# small_hopper_board.net
KiCad netlist of a schematic drawn in EAGLE
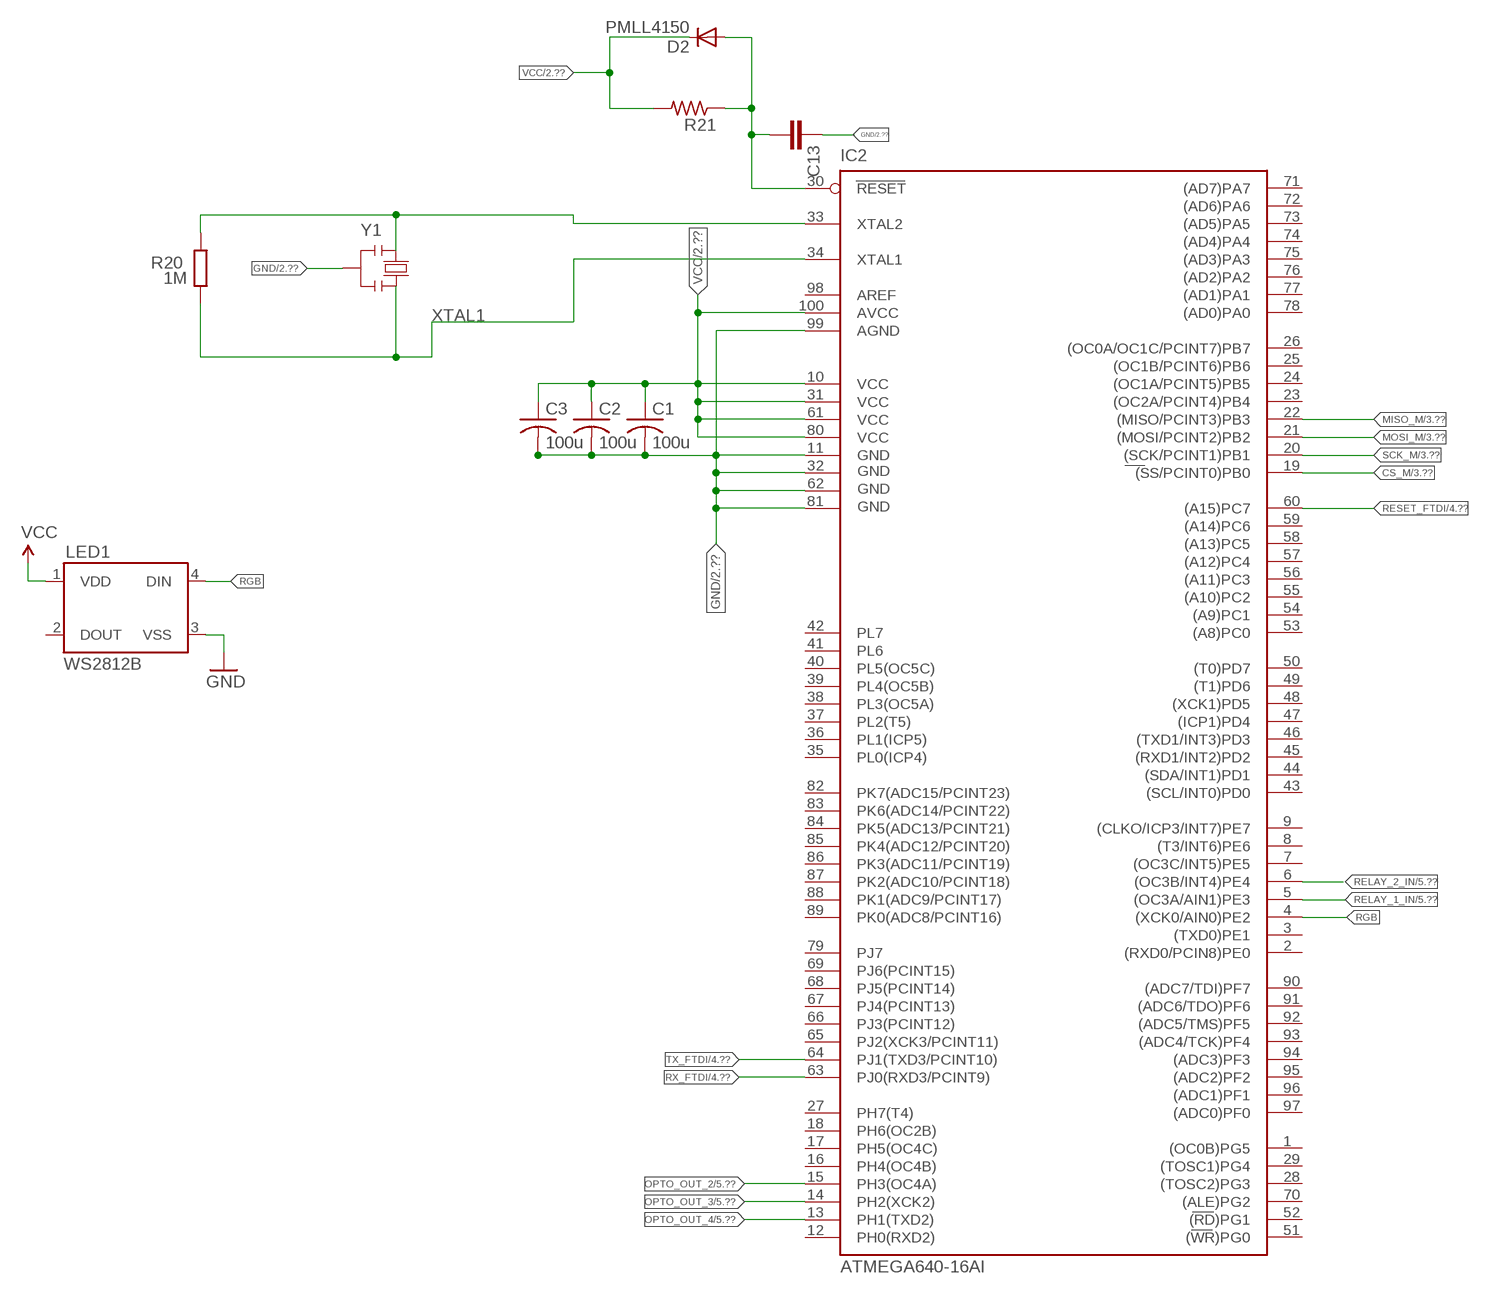
[diagram p0: schematic, sheet 1]
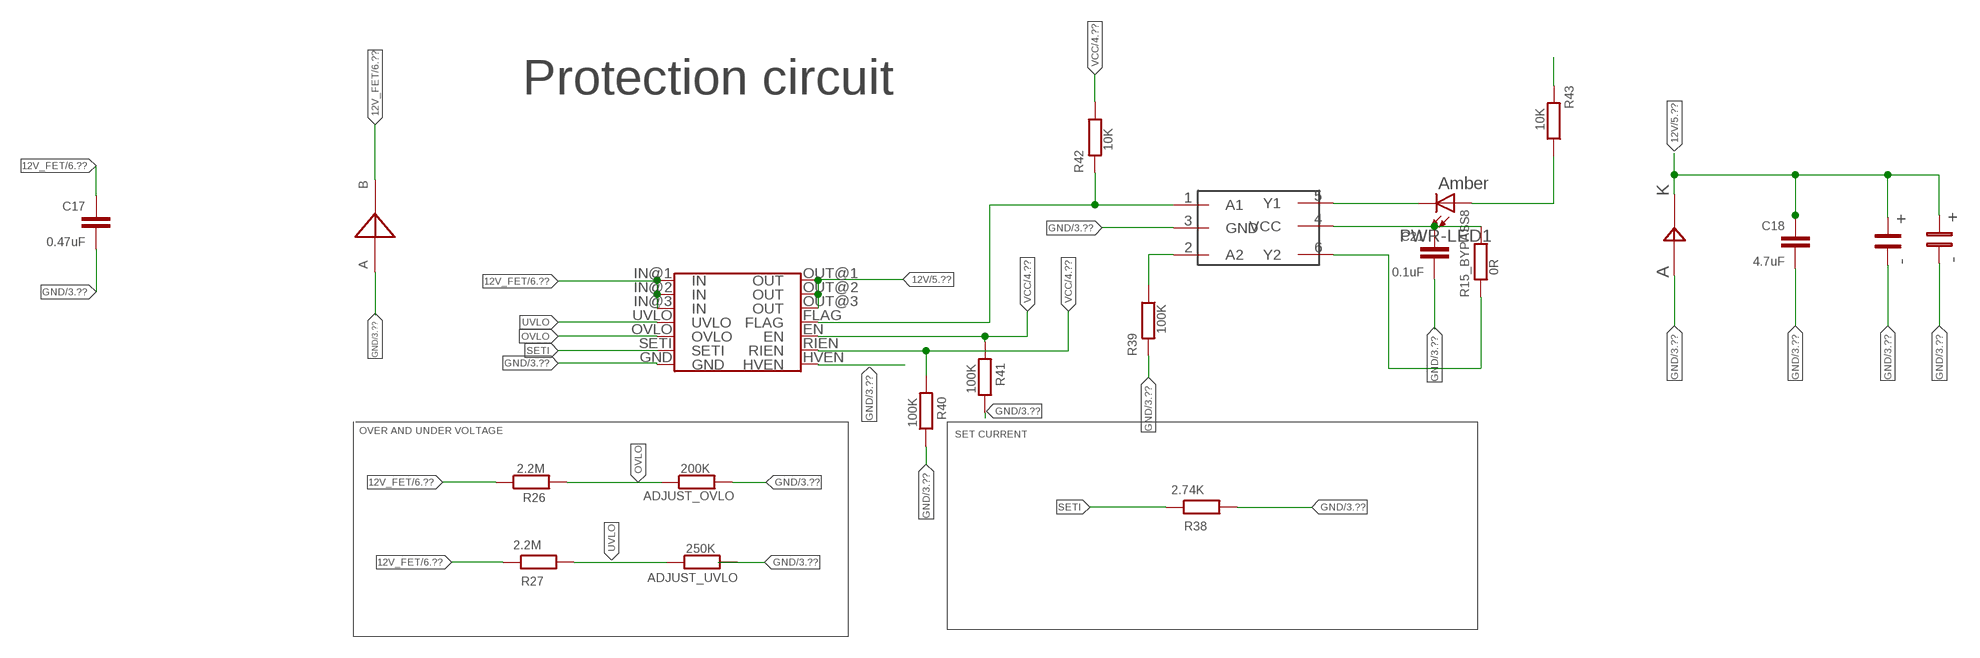
[diagram p1: schematic, sheet 2]
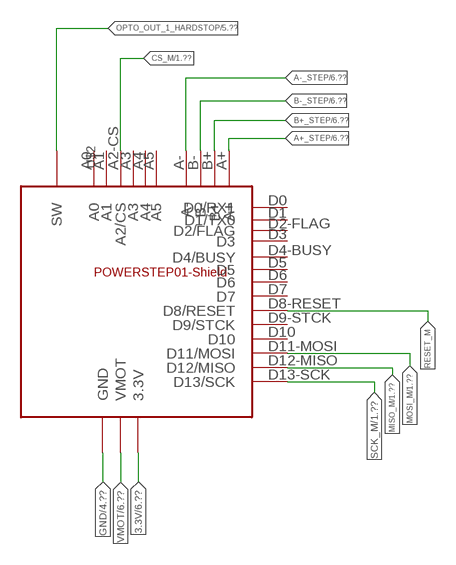
[diagram p2: schematic, sheet 3]
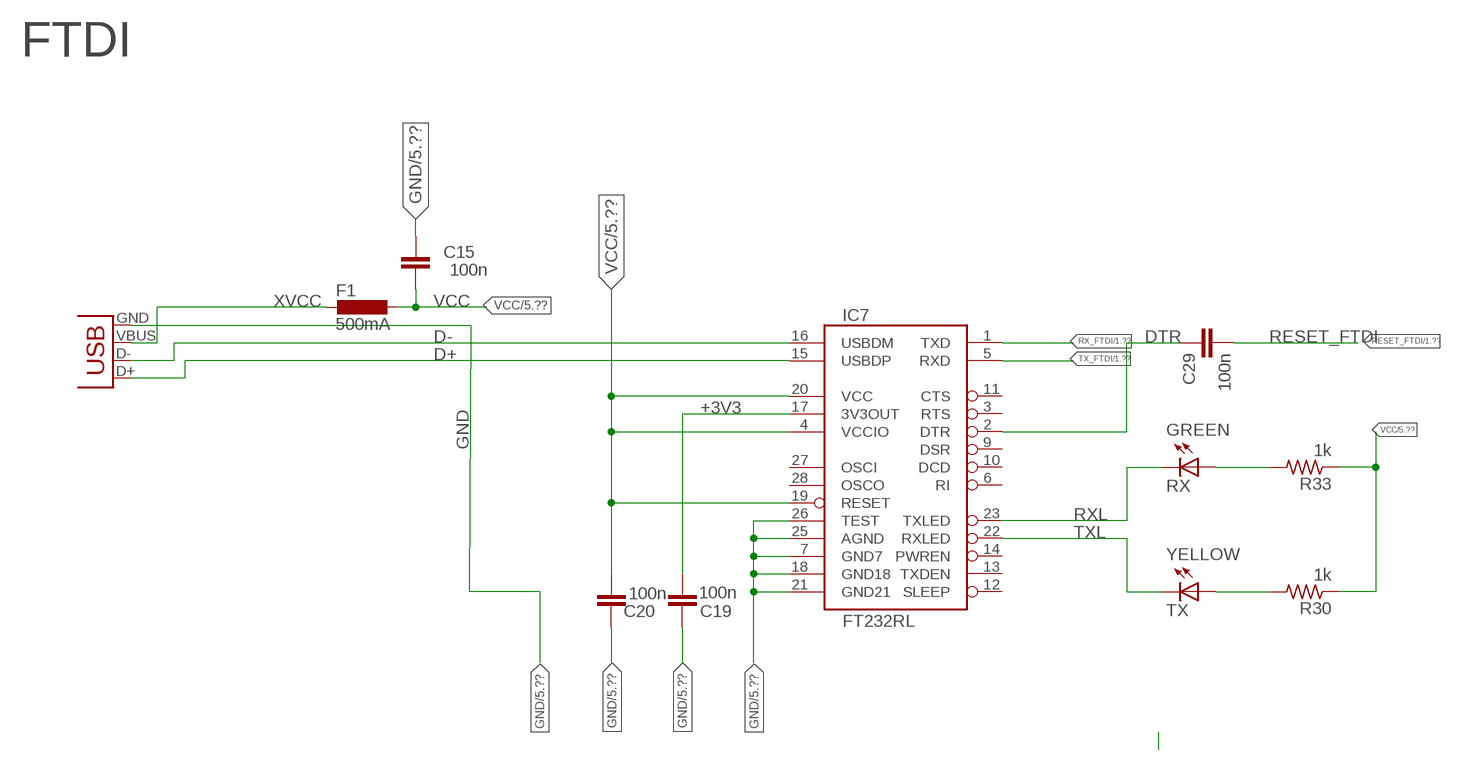
[diagram p3: schematic, sheet 4]
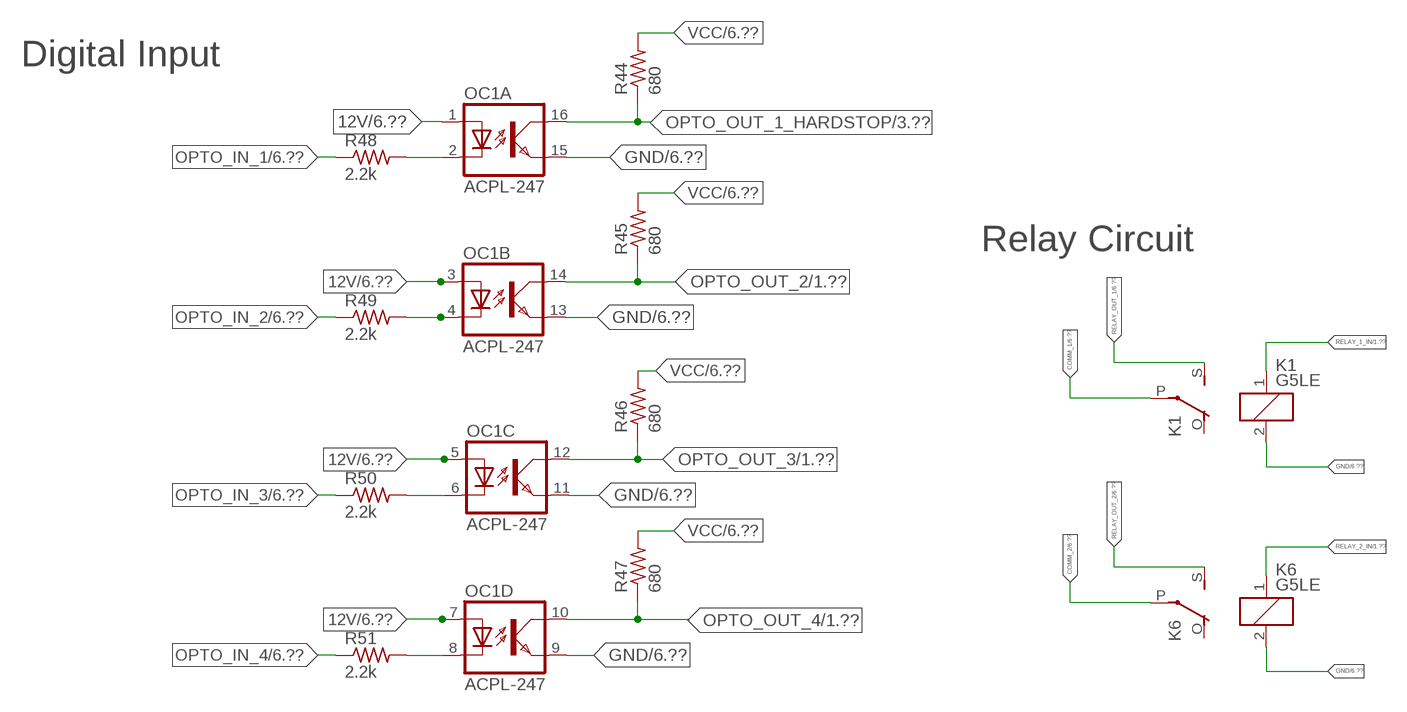
[diagram p4: schematic, sheet 5]
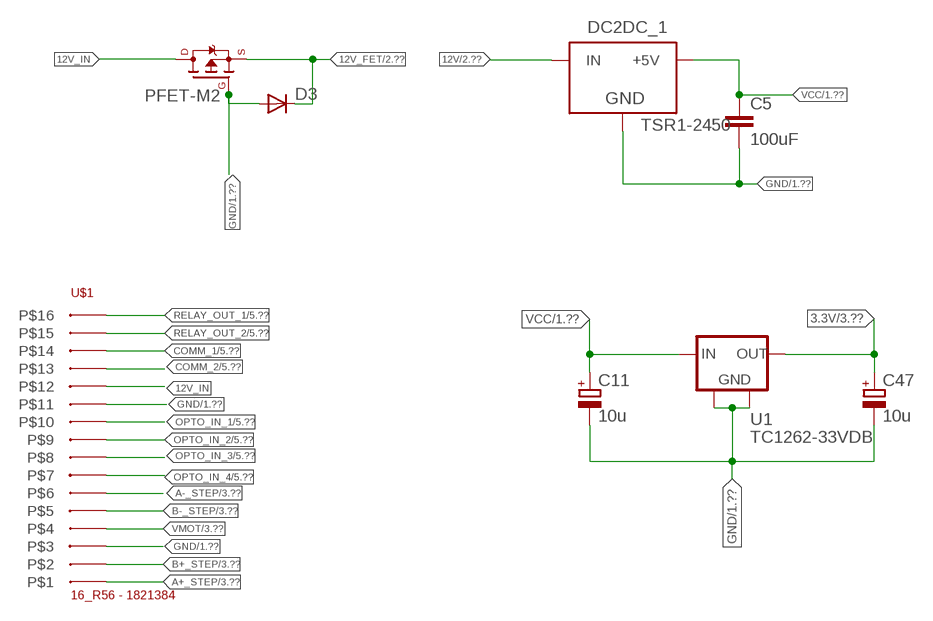
[diagram p5: schematic, sheet 6]

(export (version "E")
  (design (tool "Eeschema 10.0.6"))
  (components
    (comp (ref "C1")
      (value "100u")
      (footprint "eagle-import:C0603")
      (libsource (lib "eagle-import") (part "C-USC0603"))
    )
    (comp (ref "C2")
      (value "100u")
      (footprint "eagle-import:C0603")
      (libsource (lib "eagle-import") (part "C-USC0603"))
    )
    (comp (ref "C3")
      (value "100u")
      (footprint "eagle-import:C0603")
      (libsource (lib "eagle-import") (part "C-USC0603"))
    )
    (comp (ref "C13")
      (value "CC0603")
      (footprint "eagle-import:C0603")
      (libsource (lib "eagle-import") (part "CC0603"))
    )
    (comp (ref "D2")
      (value "PMLL4150")
      (footprint "eagle-import:SOD80C")
      (libsource (lib "eagle-import") (part "PMLL4150"))
    )
    (comp (ref "IC2")
      (value "ATMEGA640-16AI")
      (footprint "eagle-import:TQFP100")
      (libsource (lib "eagle-import") (part "ATMEGAAI640-16"))
    )
    (comp (ref "LED1")
      (value "WS2812B")
      (footprint "eagle-import:WS2812B")
      (libsource (lib "eagle-import") (part "WS2812B"))
    )
    (comp (ref "R20")
      (value "1M")
      (footprint "eagle-import:R0603-ROUND")
      (libsource (lib "eagle-import") (part "R-EU_R0603"))
    )
    (comp (ref "R21")
      (value "R-US_R0603")
      (footprint "eagle-import:R0603")
      (libsource (lib "eagle-import") (part "resistor_R-US_R0603"))
    )
    (comp (ref "Y1")
      (value "RESONATORMU")
      (footprint "eagle-import:RESONATOR")
      (libsource (lib "eagle-import") (part "RESONATORMU"))
    )
    (comp (ref "C5")
      (value "100uF")
      (footprint "eagle-import:C0603")
      (libsource (lib "eagle-import") (part "CC0603"))
    )
    (comp (ref "C11")
      (value "10u")
      (footprint "eagle-import:153CLV-0605")
      (libsource (lib "eagle-import") (part "CPOL-EU153CLV-0605"))
    )
    (comp (ref "C47")
      (value "10u")
      (footprint "eagle-import:153CLV-0605")
      (libsource (lib "eagle-import") (part "CPOL-EU153CLV-0605"))
    )
    (comp (ref "D3")
      (value "DIODE-MINIMELF")
      (footprint "eagle-import:MINIMELF")
      (libsource (lib "eagle-import") (part "DIODE-MINIMELF"))
    )
    (comp (ref "DC2DC_1")
      (value "TSR1-2450")
      (footprint "eagle-import:TSR-1")
      (libsource (lib "eagle-import") (part "TSR1-2450"))
    )
    (comp (ref "PFET-M2")
      (value "FQP47P06NORMAL")
      (footprint "eagle-import:FQP47P06-NORMAL")
      (libsource (lib "eagle-import") (part "FQP47P06NORMAL"))
    )
    (comp (ref "U$1")
      (value "16_R56 - 1821384")
      (footprint "eagle-import:16_R56 - 1821384")
      (libsource (lib "eagle-import") (part "16_R56 - 1821384"))
    )
    (comp (ref "U1")
      (value "TC1262-33VDB")
      (footprint "eagle-import:SOT223")
      (libsource (lib "eagle-import") (part "TC1262-50VDB"))
    )
    (comp (ref "K1")
      (value "G5LE")
      (footprint "eagle-import:G5LE")
      (libsource (lib "eagle-import") (part "G5LE"))
    )
    (comp (ref "K6")
      (value "G5LE")
      (footprint "eagle-import:G5LE")
      (libsource (lib "eagle-import") (part "G5LE"))
    )
    (comp (ref "OC1")
      (value "ACPL-247")
      (footprint "eagle-import:SOP16")
      (libsource (lib "eagle-import") (part "ACPL-247"))
    )
    (comp (ref "R44")
      (value "680")
      (footprint "eagle-import:R0603")
      (libsource (lib "eagle-import") (part "R-US_R0603"))
    )
    (comp (ref "R45")
      (value "680")
      (footprint "eagle-import:R0603")
      (libsource (lib "eagle-import") (part "R-US_R0603"))
    )
    (comp (ref "R46")
      (value "680")
      (footprint "eagle-import:R0603")
      (libsource (lib "eagle-import") (part "R-US_R0603"))
    )
    (comp (ref "R47")
      (value "680")
      (footprint "eagle-import:R0603")
      (libsource (lib "eagle-import") (part "R-US_R0603"))
    )
    (comp (ref "R48")
      (value "2.2k")
      (footprint "eagle-import:R0603")
      (libsource (lib "eagle-import") (part "R-US_R0603"))
    )
    (comp (ref "R49")
      (value "2.2k")
      (footprint "eagle-import:R0603")
      (libsource (lib "eagle-import") (part "R-US_R0603"))
    )
    (comp (ref "R50")
      (value "2.2k")
      (footprint "eagle-import:R0603")
      (libsource (lib "eagle-import") (part "R-US_R0603"))
    )
    (comp (ref "R51")
      (value "2.2k")
      (footprint "eagle-import:R0603")
      (libsource (lib "eagle-import") (part "R-US_R0603"))
    )
    (comp (ref "C15")
      (value "100n")
      (footprint "eagle-import:C0603")
      (libsource (lib "eagle-import") (part "rcl_C-EUC0603"))
    )
    (comp (ref "C19")
      (value "100n")
      (footprint "eagle-import:C0603-ROUND")
      (libsource (lib "eagle-import") (part "C-EU0603-RND"))
    )
    (comp (ref "C20")
      (value "100n")
      (footprint "eagle-import:C0603-ROUND")
      (libsource (lib "eagle-import") (part "C-EU0603-RND"))
    )
    (comp (ref "C29")
      (value "100n")
      (footprint "eagle-import:C0603-ROUND")
      (libsource (lib "eagle-import") (part "C-EU0603-RND"))
    )
    (comp (ref "F1")
      (value "500mA")
      (footprint "eagle-import:L1812")
      (libsource (lib "eagle-import") (part "L-EUL1812"))
    )
    (comp (ref "IC7")
      (value "FT232RL")
      (footprint "eagle-import:SSOP28DB")
      (libsource (lib "eagle-import") (part "FT232RLSSOP"))
    )
    (comp (ref "R30")
      (value "1k")
      (footprint "eagle-import:R0603")
      (libsource (lib "eagle-import") (part "resistor_R-US_R0603"))
    )
    (comp (ref "R33")
      (value "1k")
      (footprint "eagle-import:R0603")
      (libsource (lib "eagle-import") (part "resistor_R-US_R0603"))
    )
    (comp (ref "RX")
      (value "GREEN")
      (footprint "eagle-import:CHIPLED_0603")
      (libsource (lib "eagle-import") (part "LEDCHIPLED_0603"))
    )
    (comp (ref "TX")
      (value "YELLOW")
      (footprint "eagle-import:CHIPLED_0603")
      (libsource (lib "eagle-import") (part "LEDCHIPLED_0603"))
    )
    (comp (ref "USB")
      (value "USB")
      (footprint "eagle-import:USB-B-PTH-VERTICAL")
      (libsource (lib "eagle-import") (part "USBPTH-VERTICAL"))
    )
    (comp (ref "U$2")
      (value "POWERSTEP01-SHIELD")
      (footprint "eagle-import:POWERSTEP1")
      (libsource (lib "eagle-import") (part "POWERSTEP01-SHIELD"))
    )
    (comp (ref "ADJUST_OVLO")
      (value "200K")
      (footprint "eagle-import:R0603-ROUND")
      (libsource (lib "eagle-import") (part "R-EU_R0603"))
    )
    (comp (ref "ADJUST_UVLO")
      (value "250K")
      (footprint "eagle-import:R0603-ROUND")
      (libsource (lib "eagle-import") (part "R-EU_R0603"))
    )
    (comp (ref "C17")
      (value "0.47uF")
      (footprint "eagle-import:C0603-ROUND")
      (libsource (lib "eagle-import") (part "C-EU0603-RND"))
    )
    (comp (ref "C18")
      (value "4.7uF")
      (footprint "eagle-import:C0603-ROUND")
      (libsource (lib "eagle-import") (part "C-EU0603-RND"))
    )
    (comp (ref "C21")
      (value "0.1uF")
      (footprint "eagle-import:C0603-ROUND")
      (libsource (lib "eagle-import") (part "C-EU0603-RND"))
    )
    (comp (ref "PWR-LED1")
      (value "Amber")
      (footprint "eagle-import:LED-0603")
      (libsource (lib "eagle-import") (part "LED0603"))
    )
    (comp (ref "R15_BYPASS8")
      (value "0R")
      (footprint "eagle-import:R0603-ROUND")
      (libsource (lib "eagle-import") (part "R-EU_R0603"))
    )
    (comp (ref "R26")
      (value "2.2M")
      (footprint "eagle-import:R0603-ROUND")
      (libsource (lib "eagle-import") (part "R-EU_R0603"))
    )
    (comp (ref "R27")
      (value "2.2M")
      (footprint "eagle-import:R0603-ROUND")
      (libsource (lib "eagle-import") (part "R-EU_R0603"))
    )
    (comp (ref "R38")
      (value "2.74K")
      (footprint "eagle-import:R0603-ROUND")
      (libsource (lib "eagle-import") (part "R-EU_R0603"))
    )
    (comp (ref "R39")
      (value "100K")
      (footprint "eagle-import:R0603-ROUND")
      (libsource (lib "eagle-import") (part "R-EU_R0603"))
    )
    (comp (ref "R40")
      (value "100K")
      (footprint "eagle-import:R0603-ROUND")
      (libsource (lib "eagle-import") (part "R-EU_R0603"))
    )
    (comp (ref "R41")
      (value "100K")
      (footprint "eagle-import:R0603-ROUND")
      (libsource (lib "eagle-import") (part "R-EU_R0603"))
    )
    (comp (ref "R42")
      (value "10K")
      (footprint "eagle-import:R0603-ROUND")
      (libsource (lib "eagle-import") (part "R-EU_R0603"))
    )
    (comp (ref "R43")
      (value "10K")
      (footprint "eagle-import:R0603-ROUND")
      (libsource (lib "eagle-import") (part "R-EU_R0603"))
    )
    (comp (ref "U$37")
      (value "MAX14571")
      (footprint "eagle-import:TSSOP14")
      (libsource (lib "eagle-import") (part "MAX14571"))
    )
    (comp (ref "U$38")
      (value "STPS5L60S")
      (footprint "eagle-import:SMC")
      (libsource (lib "eagle-import") (part "STPS5L60S"))
    )
    (comp (ref "U$39")
      (value "SM6T36CA")
      (footprint "eagle-import:DO214AA")
      (libsource (lib "eagle-import") (part "SM6T36CA"))
    )
    (comp (ref "U$40")
      (value "NC7WZ07P6X")
      (footprint "eagle-import:SC70-6L")
      (libsource (lib "eagle-import") (part "NC7WZ07P6X"))
    )
    (comp (ref "U$41")
      (value "EEV-FK1H331Q")
      (footprint "eagle-import:EEVFK1H331Q")
      (libsource (lib "eagle-import") (part "EEV-FK1H331Q"))
    )
    (comp (ref "U$42")
      (value "EEV-FK1H331Q")
      (footprint "eagle-import:EEVFK1H331Q")
      (libsource (lib "eagle-import") (part "EEV-FK1H331Q"))
    )
  )
  (nets
    (net (code "1") (name "+3V3") (class "Default")
      (node (ref "C19") (pin "2") (pinfunction "2_2") (pintype "passive"))
      (node (ref "IC7") (pin "17") (pinfunction "3V3OUT_17") (pintype "output"))
    )
    (net (code "2") (name "3.3V") (class "Default")
      (node (ref "C47") (pin "+") (pinfunction "+_+") (pintype "passive"))
      (node (ref "U$2") (pin "3.3V") (pinfunction "3.3V_3.3V") (pintype "power_in"))
      (node (ref "U$2") (pin "IOREF") (pinfunction "3.3V_IOREF") (pintype "power_in"))
      (node (ref "U1") (pin "3") (pinfunction "OUT_3") (pintype "passive"))
    )
    (net (code "3") (name "12V") (class "Default")
      (node (ref "C18") (pin "1") (pinfunction "1_1") (pintype "passive"))
      (node (ref "DC2DC_1") (pin "1") (pinfunction "IN_1") (pintype "power_in"))
      (node (ref "OC1") (pin "1") (pinfunction "A_1") (pintype "passive"))
      (node (ref "OC1") (pin "3") (pinfunction "A_3") (pintype "passive"))
      (node (ref "OC1") (pin "5") (pinfunction "A_5") (pintype "passive"))
      (node (ref "OC1") (pin "7") (pinfunction "A_7") (pintype "passive"))
      (node (ref "U$37") (pin "OUT@1") (pinfunction "OUT_OUT@1") (pintype "bidirectional"))
      (node (ref "U$37") (pin "OUT@2") (pinfunction "OUT_OUT@2") (pintype "bidirectional"))
      (node (ref "U$37") (pin "OUT@3") (pinfunction "OUT_OUT@3") (pintype "bidirectional"))
      (node (ref "U$38") (pin "1") (pinfunction "P$2_1") (pintype "bidirectional"))
      (node (ref "U$41") (pin "P$2") (pinfunction "P$1_P$2") (pintype "bidirectional"))
      (node (ref "U$42") (pin "P$2") (pinfunction "P$1_P$2") (pintype "bidirectional"))
    )
    (net (code "4") (name "12V_FET") (class "Default")
      (node (ref "C17") (pin "1") (pinfunction "1_1") (pintype "passive"))
      (node (ref "D3") (pin "C") (pinfunction "C_C") (pintype "passive"))
      (node (ref "PFET-M2") (pin "3") (pinfunction "S_3") (pintype "passive"))
      (node (ref "R26") (pin "1") (pinfunction "1_1") (pintype "passive"))
      (node (ref "R27") (pin "1") (pinfunction "1_1") (pintype "passive"))
      (node (ref "U$37") (pin "IN@1") (pinfunction "IN_IN@1") (pintype "bidirectional"))
      (node (ref "U$37") (pin "IN@2") (pinfunction "IN_IN@2") (pintype "bidirectional"))
      (node (ref "U$37") (pin "IN@3") (pinfunction "IN_IN@3") (pintype "bidirectional"))
      (node (ref "U$39") (pin "C") (pinfunction "P$2_C") (pintype "bidirectional"))
    )
    (net (code "5") (name "12V_IN") (class "Default")
      (node (ref "PFET-M2") (pin "2") (pinfunction "D_2") (pintype "passive"))
      (node (ref "U$1") (pin "P$12") (pinfunction "P$12_P$12") (pintype "bidirectional"))
    )
    (net (code "6") (name "A+_STEP") (class "Default")
      (node (ref "U$1") (pin "P$1") (pinfunction "P$1_P$1") (pintype "bidirectional"))
      (node (ref "U$2") (pin "A+") (pinfunction "A+_A+") (pintype "bidirectional"))
    )
    (net (code "7") (name "A-_STEP") (class "Default")
      (node (ref "U$1") (pin "P$6") (pinfunction "P$6_P$6") (pintype "bidirectional"))
      (node (ref "U$2") (pin "A-") (pinfunction "A-_A-") (pintype "bidirectional"))
    )
    (net (code "8") (name "B+_STEP") (class "Default")
      (node (ref "U$1") (pin "P$2") (pinfunction "P$2_P$2") (pintype "bidirectional"))
      (node (ref "U$2") (pin "B+") (pinfunction "B+_B+") (pintype "bidirectional"))
    )
    (net (code "9") (name "B-_STEP") (class "Default")
      (node (ref "U$1") (pin "P$5") (pinfunction "P$5_P$5") (pintype "bidirectional"))
      (node (ref "U$2") (pin "B-") (pinfunction "B-_B-") (pintype "bidirectional"))
    )
    (net (code "10") (name "COMM_1") (class "Default")
      (node (ref "K1") (pin "P") (pinfunction "P_P") (pintype "passive"))
      (node (ref "U$1") (pin "P$14") (pinfunction "P$14_P$14") (pintype "bidirectional"))
    )
    (net (code "11") (name "COMM_2") (class "Default")
      (node (ref "K6") (pin "P") (pinfunction "P_P") (pintype "passive"))
      (node (ref "U$1") (pin "P$13") (pinfunction "P$13_P$13") (pintype "bidirectional"))
    )
    (net (code "12") (name "CS_M") (class "Default")
      (node (ref "IC2") (pin "19") (pinfunction "(SS/PCINT0)PB0_19") (pintype "bidirectional"))
      (node (ref "U$2") (pin "A2-CS") (pinfunction "A2/CS_A2-CS") (pintype "bidirectional"))
    )
    (net (code "13") (name "D+") (class "Default")
      (node (ref "IC7") (pin "15") (pinfunction "USBDP_15") (pintype "bidirectional"))
      (node (ref "USB") (pin "D+") (pinfunction "D+_D+") (pintype "bidirectional"))
    )
    (net (code "14") (name "D-") (class "Default")
      (node (ref "IC7") (pin "16") (pinfunction "USBDM_16") (pintype "bidirectional"))
      (node (ref "USB") (pin "D-") (pinfunction "D-_D-") (pintype "bidirectional"))
    )
    (net (code "15") (name "DTR") (class "Default")
      (node (ref "C29") (pin "1") (pinfunction "1_1") (pintype "passive"))
      (node (ref "IC7") (pin "2") (pinfunction "DTR_2") (pintype "output"))
    )
    (net (code "16") (name "GND") (class "Default")
      (node (ref "ADJUST_OVLO") (pin "2") (pinfunction "2_2") (pintype "passive"))
      (node (ref "ADJUST_UVLO") (pin "2") (pinfunction "2_2") (pintype "passive"))
      (node (ref "C1") (pin "2") (pinfunction "2_2") (pintype "passive"))
      (node (ref "C11") (pin "-") (pinfunction "-_-") (pintype "passive"))
      (node (ref "C13") (pin "1") (pinfunction "1_1") (pintype "passive"))
      (node (ref "C15") (pin "2") (pinfunction "2_2") (pintype "passive"))
      (node (ref "C17") (pin "2") (pinfunction "2_2") (pintype "passive"))
      (node (ref "C18") (pin "2") (pinfunction "2_2") (pintype "passive"))
      (node (ref "C19") (pin "1") (pinfunction "1_1") (pintype "passive"))
      (node (ref "C2") (pin "2") (pinfunction "2_2") (pintype "passive"))
      (node (ref "C20") (pin "2") (pinfunction "2_2") (pintype "passive"))
      (node (ref "C21") (pin "2") (pinfunction "2_2") (pintype "passive"))
      (node (ref "C3") (pin "2") (pinfunction "2_2") (pintype "passive"))
      (node (ref "C47") (pin "-") (pinfunction "-_-") (pintype "passive"))
      (node (ref "C5") (pin "2") (pinfunction "2_2") (pintype "passive"))
      (node (ref "D3") (pin "A") (pinfunction "A_A") (pintype "passive"))
      (node (ref "DC2DC_1") (pin "2") (pinfunction "GND_2") (pintype "power_in"))
      (node (ref "IC2") (pin "11") (pinfunction "GND_11") (pintype "power_in"))
      (node (ref "IC2") (pin "32") (pinfunction "GND1_32") (pintype "power_in"))
      (node (ref "IC2") (pin "62") (pinfunction "GND2_62") (pintype "power_in"))
      (node (ref "IC2") (pin "81") (pinfunction "GND3_81") (pintype "power_in"))
      (node (ref "IC2") (pin "99") (pinfunction "AGND_99") (pintype "power_in"))
      (node (ref "IC7") (pin "18") (pinfunction "GND18_18") (pintype "power_in"))
      (node (ref "IC7") (pin "21") (pinfunction "GND21_21") (pintype "power_in"))
      (node (ref "IC7") (pin "25") (pinfunction "AGND_25") (pintype "power_in"))
      (node (ref "IC7") (pin "26") (pinfunction "TEST_26") (pintype "input"))
      (node (ref "IC7") (pin "7") (pinfunction "GND7_7") (pintype "power_in"))
      (node (ref "K1") (pin "2") (pinfunction "2_2") (pintype "passive"))
      (node (ref "K6") (pin "2") (pinfunction "2_2") (pintype "passive"))
      (node (ref "LED1") (pin "3") (pinfunction "VSS_3") (pintype "power_in"))
      (node (ref "OC1") (pin "11") (pinfunction "EMIT_11") (pintype "passive"))
      (node (ref "OC1") (pin "13") (pinfunction "EMIT_13") (pintype "passive"))
      (node (ref "OC1") (pin "15") (pinfunction "EMIT_15") (pintype "passive"))
      (node (ref "OC1") (pin "9") (pinfunction "EMIT_9") (pintype "passive"))
      (node (ref "PFET-M2") (pin "1") (pinfunction "G_1") (pintype "passive"))
      (node (ref "R38") (pin "2") (pinfunction "2_2") (pintype "passive"))
      (node (ref "R39") (pin "2") (pinfunction "2_2") (pintype "passive"))
      (node (ref "R40") (pin "1") (pinfunction "1_1") (pintype "passive"))
      (node (ref "R41") (pin "1") (pinfunction "1_1") (pintype "passive"))
      (node (ref "U$1") (pin "P$11") (pinfunction "P$11_P$11") (pintype "bidirectional"))
      (node (ref "U$1") (pin "P$3") (pinfunction "P$3_P$3") (pintype "bidirectional"))
      (node (ref "U$2") (pin "GND@0") (pinfunction "GND_GND@0") (pintype "power_in"))
      (node (ref "U$2") (pin "GND@1") (pinfunction "GND_GND@1") (pintype "power_in"))
      (node (ref "U$2") (pin "GND@2") (pinfunction "GND_GND@2") (pintype "power_in"))
      (node (ref "U$2") (pin "GND@3") (pinfunction "GND_GND@3") (pintype "power_in"))
      (node (ref "U$37") (pin "GND") (pinfunction "GND_GND") (pintype "bidirectional"))
      (node (ref "U$37") (pin "HVEN") (pinfunction "HVEN_HVEN") (pintype "bidirectional"))
      (node (ref "U$38") (pin "2") (pinfunction "P$1_2") (pintype "bidirectional"))
      (node (ref "U$39") (pin "A") (pinfunction "P$1_A") (pintype "bidirectional"))
      (node (ref "U$40") (pin "3") (pinfunction "GND_3") (pintype "bidirectional"))
      (node (ref "U$41") (pin "P$1") (pinfunction "P$2_P$1") (pintype "bidirectional"))
      (node (ref "U$42") (pin "P$1") (pinfunction "P$2_P$1") (pintype "bidirectional"))
      (node (ref "U1") (pin "2") (pinfunction "GND_2") (pintype "input"))
      (node (ref "U1") (pin "4") (pinfunction "GND_4") (pintype "input"))
      (node (ref "USB") (pin "GND") (pinfunction "GND_GND") (pintype "bidirectional"))
      (node (ref "Y1") (pin "2") (pinfunction "2_2") (pintype "passive"))
    )
    (net (code "17") (name "MISO_M") (class "Default")
      (node (ref "IC2") (pin "22") (pinfunction "(MISO/PCINT3)PB3_22") (pintype "bidirectional"))
      (node (ref "U$2") (pin "D12-MISO") (pinfunction "D12/MISO_D12-MISO") (pintype "bidirectional"))
    )
    (net (code "18") (name "MOSI_M") (class "Default")
      (node (ref "IC2") (pin "21") (pinfunction "(MOSI/PCINT2)PB2_21") (pintype "bidirectional"))
      (node (ref "U$2") (pin "D11-MOSI") (pinfunction "D11/MOSI_D11-MOSI") (pintype "bidirectional"))
    )
    (net (code "19") (name "Net-(IC2-RESET)") (class "Default")
      (node (ref "C13") (pin "2") (pinfunction "2_2") (pintype "passive"))
      (node (ref "D2") (pin "A") (pinfunction "A_A") (pintype "passive"))
      (node (ref "IC2") (pin "30") (pinfunction "RESET_30") (pintype "input"))
      (node (ref "R21") (pin "1") (pinfunction "1_1") (pintype "passive"))
    )
    (net (code "20") (name "Net-(IC2-XTAL2)") (class "Default")
      (node (ref "IC2") (pin "33") (pinfunction "XTAL2_33") (pintype "output"))
      (node (ref "R20") (pin "2") (pinfunction "2_2") (pintype "passive"))
      (node (ref "Y1") (pin "1") (pinfunction "1_1") (pintype "passive"))
    )
    (net (code "21") (name "Net-(OC1A-C)") (class "Default")
      (node (ref "OC1") (pin "2") (pinfunction "C_2") (pintype "passive"))
      (node (ref "R48") (pin "2") (pinfunction "2_2") (pintype "passive"))
    )
    (net (code "22") (name "Net-(OC1B-C)") (class "Default")
      (node (ref "OC1") (pin "4") (pinfunction "C_4") (pintype "passive"))
      (node (ref "R49") (pin "2") (pinfunction "2_2") (pintype "passive"))
    )
    (net (code "23") (name "Net-(OC1C-C)") (class "Default")
      (node (ref "OC1") (pin "6") (pinfunction "C_6") (pintype "passive"))
      (node (ref "R50") (pin "2") (pinfunction "2_2") (pintype "passive"))
    )
    (net (code "24") (name "Net-(OC1D-C)") (class "Default")
      (node (ref "OC1") (pin "8") (pinfunction "C_8") (pintype "passive"))
      (node (ref "R51") (pin "2") (pinfunction "2_2") (pintype "passive"))
    )
    (net (code "25") (name "Net-(PWR-LED1-PadA)") (class "Default")
      (node (ref "PWR-LED1") (pin "A") (pinfunction "A_A") (pintype "passive"))
      (node (ref "R43") (pin "1") (pinfunction "1_1") (pintype "passive"))
    )
    (net (code "26") (name "Net-(R30-Pad2)") (class "Default")
      (node (ref "R30") (pin "2") (pinfunction "2_2") (pintype "passive"))
      (node (ref "TX") (pin "A") (pinfunction "A_A") (pintype "passive"))
    )
    (net (code "27") (name "Net-(R33-Pad2)") (class "Default")
      (node (ref "R33") (pin "2") (pinfunction "2_2") (pintype "passive"))
      (node (ref "RX") (pin "A") (pinfunction "A_A") (pintype "passive"))
    )
    (net (code "28") (name "Net-(U$40-A1)") (class "Default")
      (node (ref "R42") (pin "2") (pinfunction "2_2") (pintype "passive"))
      (node (ref "U$37") (pin "FLAG") (pinfunction "FLAG_FLAG") (pintype "bidirectional"))
      (node (ref "U$40") (pin "1") (pinfunction "A1_1") (pintype "bidirectional"))
    )
    (net (code "29") (name "Net-(U$40-A2)") (class "Default")
      (node (ref "R39") (pin "1") (pinfunction "1_1") (pintype "passive"))
      (node (ref "U$40") (pin "2") (pinfunction "A2_2") (pintype "bidirectional"))
    )
    (net (code "30") (name "Net-(U$40-Y1)") (class "Default")
      (node (ref "PWR-LED1") (pin "C") (pinfunction "C_C") (pintype "passive"))
      (node (ref "U$40") (pin "5") (pinfunction "Y1_5") (pintype "bidirectional"))
    )
    (net (code "31") (name "Net-(U$40-Y2)") (class "Default")
      (node (ref "R15_BYPASS8") (pin "2") (pinfunction "2_2") (pintype "passive"))
      (node (ref "U$40") (pin "6") (pinfunction "Y2_6") (pintype "bidirectional"))
    )
    (net (code "32") (name "OPTO_IN_1") (class "Default")
      (node (ref "R48") (pin "1") (pinfunction "1_1") (pintype "passive"))
      (node (ref "U$1") (pin "P$10") (pinfunction "P$10_P$10") (pintype "bidirectional"))
    )
    (net (code "33") (name "OPTO_IN_2") (class "Default")
      (node (ref "R49") (pin "1") (pinfunction "1_1") (pintype "passive"))
      (node (ref "U$1") (pin "P$9") (pinfunction "P$9_P$9") (pintype "bidirectional"))
    )
    (net (code "34") (name "OPTO_IN_3") (class "Default")
      (node (ref "R50") (pin "1") (pinfunction "1_1") (pintype "passive"))
      (node (ref "U$1") (pin "P$8") (pinfunction "P$8_P$8") (pintype "bidirectional"))
    )
    (net (code "35") (name "OPTO_IN_4") (class "Default")
      (node (ref "R51") (pin "1") (pinfunction "1_1") (pintype "passive"))
      (node (ref "U$1") (pin "P$7") (pinfunction "P$7_P$7") (pintype "bidirectional"))
    )
    (net (code "36") (name "OPTO_OUT_1_HARDSTOP") (class "Default")
      (node (ref "OC1") (pin "16") (pinfunction "COL_16") (pintype "passive"))
      (node (ref "R44") (pin "1") (pinfunction "1_1") (pintype "passive"))
      (node (ref "U$2") (pin "SW") (pinfunction "SW_SW") (pintype "input"))
    )
    (net (code "37") (name "OPTO_OUT_2") (class "Default")
      (node (ref "IC2") (pin "15") (pinfunction "PH3(OC4A)_15") (pintype "bidirectional"))
      (node (ref "OC1") (pin "14") (pinfunction "COL_14") (pintype "passive"))
      (node (ref "R45") (pin "1") (pinfunction "1_1") (pintype "passive"))
    )
    (net (code "38") (name "OPTO_OUT_3") (class "Default")
      (node (ref "IC2") (pin "14") (pinfunction "PH2(XCK2)_14") (pintype "bidirectional"))
      (node (ref "OC1") (pin "12") (pinfunction "COL_12") (pintype "passive"))
      (node (ref "R46") (pin "1") (pinfunction "1_1") (pintype "passive"))
    )
    (net (code "39") (name "OPTO_OUT_4") (class "Default")
      (node (ref "IC2") (pin "13") (pinfunction "PH1(TXD2)_13") (pintype "bidirectional"))
      (node (ref "OC1") (pin "10") (pinfunction "COL_10") (pintype "passive"))
      (node (ref "R47") (pin "1") (pinfunction "1_1") (pintype "passive"))
    )
    (net (code "40") (name "OVLO") (class "Default")
      (node (ref "ADJUST_OVLO") (pin "1") (pinfunction "1_1") (pintype "passive"))
      (node (ref "R26") (pin "2") (pinfunction "2_2") (pintype "passive"))
      (node (ref "U$37") (pin "OVLO") (pinfunction "OVLO_OVLO") (pintype "bidirectional"))
    )
    (net (code "41") (name "RELAY_1_IN") (class "Default")
      (node (ref "IC2") (pin "5") (pinfunction "(OC3A/AIN1)PE3_5") (pintype "bidirectional"))
      (node (ref "K1") (pin "1") (pinfunction "1_1") (pintype "passive"))
    )
    (net (code "42") (name "RELAY_2_IN") (class "Default")
      (node (ref "IC2") (pin "6") (pinfunction "(OC3B/INT4)PE4_6") (pintype "bidirectional"))
      (node (ref "K6") (pin "1") (pinfunction "1_1") (pintype "passive"))
    )
    (net (code "43") (name "RELAY_OUT_1") (class "Default")
      (node (ref "K1") (pin "S") (pinfunction "S_S") (pintype "passive"))
      (node (ref "U$1") (pin "P$16") (pinfunction "P$16_P$16") (pintype "bidirectional"))
    )
    (net (code "44") (name "RELAY_OUT_2") (class "Default")
      (node (ref "K6") (pin "S") (pinfunction "S_S") (pintype "passive"))
      (node (ref "U$1") (pin "P$15") (pinfunction "P$15_P$15") (pintype "bidirectional"))
    )
    (net (code "45") (name "RESET_FTDI") (class "Default")
      (node (ref "C29") (pin "2") (pinfunction "2_2") (pintype "passive"))
      (node (ref "IC2") (pin "60") (pinfunction "(A15)PC7_60") (pintype "bidirectional"))
    )
    (net (code "46") (name "RESET_M") (class "Default")
      (node (ref "U$2") (pin "D8-RESET") (pinfunction "D8/RESET_D8-RESET") (pintype "bidirectional"))
    )
    (net (code "47") (name "RGB") (class "Default")
      (node (ref "IC2") (pin "4") (pinfunction "(XCK0/AIN0)PE2_4") (pintype "bidirectional"))
      (node (ref "LED1") (pin "4") (pinfunction "DIN_4") (pintype "input"))
    )
    (net (code "48") (name "RXL") (class "Default")
      (node (ref "IC7") (pin "23") (pinfunction "TXLED_23") (pintype "input"))
      (node (ref "RX") (pin "C") (pinfunction "C_C") (pintype "passive"))
    )
    (net (code "49") (name "RX_FTDI") (class "Default")
      (node (ref "IC2") (pin "63") (pinfunction "PJ0(RXD3/PCINT9)_63") (pintype "bidirectional"))
      (node (ref "IC7") (pin "1") (pinfunction "TXD_1") (pintype "output"))
    )
    (net (code "50") (name "SCK_M") (class "Default")
      (node (ref "IC2") (pin "20") (pinfunction "(SCK/PCINT1)PB1_20") (pintype "bidirectional"))
      (node (ref "U$2") (pin "D13-SCK") (pinfunction "D13/SCK_D13-SCK") (pintype "bidirectional"))
    )
    (net (code "51") (name "SETI") (class "Default")
      (node (ref "R38") (pin "1") (pinfunction "1_1") (pintype "passive"))
      (node (ref "U$37") (pin "SETI") (pinfunction "SETI_SETI") (pintype "bidirectional"))
    )
    (net (code "52") (name "TXL") (class "Default")
      (node (ref "IC7") (pin "22") (pinfunction "RXLED_22") (pintype "input"))
      (node (ref "TX") (pin "C") (pinfunction "C_C") (pintype "passive"))
    )
    (net (code "53") (name "TX_FTDI") (class "Default")
      (node (ref "IC2") (pin "64") (pinfunction "PJ1(TXD3/PCINT10)_64") (pintype "bidirectional"))
      (node (ref "IC7") (pin "5") (pinfunction "RXD_5") (pintype "input"))
    )
    (net (code "54") (name "UVLO") (class "Default")
      (node (ref "ADJUST_UVLO") (pin "1") (pinfunction "1_1") (pintype "passive"))
      (node (ref "R27") (pin "2") (pinfunction "2_2") (pintype "passive"))
      (node (ref "U$37") (pin "UVLO") (pinfunction "UVLO_UVLO") (pintype "bidirectional"))
    )
    (net (code "55") (name "VCC") (class "Default")
      (node (ref "C1") (pin "1") (pinfunction "1_1") (pintype "passive"))
      (node (ref "C11") (pin "+") (pinfunction "+_+") (pintype "passive"))
      (node (ref "C15") (pin "1") (pinfunction "1_1") (pintype "passive"))
      (node (ref "C2") (pin "1") (pinfunction "1_1") (pintype "passive"))
      (node (ref "C20") (pin "1") (pinfunction "1_1") (pintype "passive"))
      (node (ref "C21") (pin "1") (pinfunction "1_1") (pintype "passive"))
      (node (ref "C3") (pin "1") (pinfunction "1_1") (pintype "passive"))
      (node (ref "C5") (pin "1") (pinfunction "1_1") (pintype "passive"))
      (node (ref "D2") (pin "C") (pinfunction "C_C") (pintype "passive"))
      (node (ref "DC2DC_1") (pin "3") (pinfunction "+5V_3") (pintype "power_in"))
      (node (ref "F1") (pin "1") (pinfunction "1_1") (pintype "passive"))
      (node (ref "IC2") (pin "10") (pinfunction "VCC_10") (pintype "power_in"))
      (node (ref "IC2") (pin "100") (pinfunction "AVCC_100") (pintype "power_in"))
      (node (ref "IC2") (pin "31") (pinfunction "VCC1_31") (pintype "power_in"))
      (node (ref "IC2") (pin "61") (pinfunction "VCC2_61") (pintype "power_in"))
      (node (ref "IC2") (pin "80") (pinfunction "VCC3_80") (pintype "power_in"))
      (node (ref "IC7") (pin "19") (pinfunction "RESET_19") (pintype "input"))
      (node (ref "IC7") (pin "20") (pinfunction "VCC_20") (pintype "power_in"))
      (node (ref "IC7") (pin "4") (pinfunction "VCCIO_4") (pintype "power_in"))
      (node (ref "LED1") (pin "1") (pinfunction "VDD_1") (pintype "power_in"))
      (node (ref "R15_BYPASS8") (pin "1") (pinfunction "1_1") (pintype "passive"))
      (node (ref "R21") (pin "2") (pinfunction "2_2") (pintype "passive"))
      (node (ref "R30") (pin "1") (pinfunction "1_1") (pintype "passive"))
      (node (ref "R33") (pin "1") (pinfunction "1_1") (pintype "passive"))
      (node (ref "R40") (pin "2") (pinfunction "2_2") (pintype "passive"))
      (node (ref "R41") (pin "2") (pinfunction "2_2") (pintype "passive"))
      (node (ref "R42") (pin "1") (pinfunction "1_1") (pintype "passive"))
      (node (ref "R43") (pin "2") (pinfunction "2_2") (pintype "passive"))
      (node (ref "R44") (pin "2") (pinfunction "2_2") (pintype "passive"))
      (node (ref "R45") (pin "2") (pinfunction "2_2") (pintype "passive"))
      (node (ref "R46") (pin "2") (pinfunction "2_2") (pintype "passive"))
      (node (ref "R47") (pin "2") (pinfunction "2_2") (pintype "passive"))
      (node (ref "U$37") (pin "EN") (pinfunction "EN_EN") (pintype "bidirectional"))
      (node (ref "U$37") (pin "RIEN") (pinfunction "RIEN_RIEN") (pintype "bidirectional"))
      (node (ref "U$40") (pin "4") (pinfunction "VCC_4") (pintype "bidirectional"))
      (node (ref "U1") (pin "1") (pinfunction "IN_1") (pintype "input"))
    )
    (net (code "56") (name "VMOT") (class "Default")
      (node (ref "U$1") (pin "P$4") (pinfunction "P$4_P$4") (pintype "bidirectional"))
      (node (ref "U$2") (pin "VS+") (pinfunction "VMOT_VS+") (pintype "power_in"))
    )
    (net (code "57") (name "XTAL1") (class "Default")
      (node (ref "IC2") (pin "34") (pinfunction "XTAL1_34") (pintype "input"))
      (node (ref "R20") (pin "1") (pinfunction "1_1") (pintype "passive"))
      (node (ref "Y1") (pin "3") (pinfunction "3_3") (pintype "passive"))
    )
    (net (code "58") (name "XVCC") (class "Default")
      (node (ref "F1") (pin "2") (pinfunction "2_2") (pintype "passive"))
      (node (ref "USB") (pin "VBUS") (pinfunction "VBUS_VBUS") (pintype "bidirectional"))
    )
    (net (code "59") (name "unconnected-(IC2-(A8)PC0-Pad53)") (class "Default")
      (node (ref "IC2") (pin "53") (pinfunction "(A8)PC0_53") (pintype "bidirectional"))
    )
    (net (code "60") (name "unconnected-(IC2-(A9)PC1-Pad54)") (class "Default")
      (node (ref "IC2") (pin "54") (pinfunction "(A9)PC1_54") (pintype "bidirectional"))
    )
    (net (code "61") (name "unconnected-(IC2-(A10)PC2-Pad55)") (class "Default")
      (node (ref "IC2") (pin "55") (pinfunction "(A10)PC2_55") (pintype "bidirectional"))
    )
    (net (code "62") (name "unconnected-(IC2-(A11)PC3-Pad56)") (class "Default")
      (node (ref "IC2") (pin "56") (pinfunction "(A11)PC3_56") (pintype "bidirectional"))
    )
    (net (code "63") (name "unconnected-(IC2-(A12)PC4-Pad57)") (class "Default")
      (node (ref "IC2") (pin "57") (pinfunction "(A12)PC4_57") (pintype "bidirectional"))
    )
    (net (code "64") (name "unconnected-(IC2-(A13)PC5-Pad58)") (class "Default")
      (node (ref "IC2") (pin "58") (pinfunction "(A13)PC5_58") (pintype "bidirectional"))
    )
    (net (code "65") (name "unconnected-(IC2-(A14)PC6-Pad59)") (class "Default")
      (node (ref "IC2") (pin "59") (pinfunction "(A14)PC6_59") (pintype "bidirectional"))
    )
    (net (code "66") (name "unconnected-(IC2-(AD0)PA0-Pad78)") (class "Default")
      (node (ref "IC2") (pin "78") (pinfunction "(AD0)PA0_78") (pintype "bidirectional"))
    )
    (net (code "67") (name "unconnected-(IC2-(AD1)PA1-Pad77)") (class "Default")
      (node (ref "IC2") (pin "77") (pinfunction "(AD1)PA1_77") (pintype "bidirectional"))
    )
    (net (code "68") (name "unconnected-(IC2-(AD2)PA2-Pad76)") (class "Default")
      (node (ref "IC2") (pin "76") (pinfunction "(AD2)PA2_76") (pintype "bidirectional"))
    )
    (net (code "69") (name "unconnected-(IC2-(AD3)PA3-Pad75)") (class "Default")
      (node (ref "IC2") (pin "75") (pinfunction "(AD3)PA3_75") (pintype "bidirectional"))
    )
    (net (code "70") (name "unconnected-(IC2-(AD4)PA4-Pad74)") (class "Default")
      (node (ref "IC2") (pin "74") (pinfunction "(AD4)PA4_74") (pintype "bidirectional"))
    )
    (net (code "71") (name "unconnected-(IC2-(AD5)PA5-Pad73)") (class "Default")
      (node (ref "IC2") (pin "73") (pinfunction "(AD5)PA5_73") (pintype "bidirectional"))
    )
    (net (code "72") (name "unconnected-(IC2-(AD6)PA6-Pad72)") (class "Default")
      (node (ref "IC2") (pin "72") (pinfunction "(AD6)PA6_72") (pintype "bidirectional"))
    )
    (net (code "73") (name "unconnected-(IC2-(AD7)PA7-Pad71)") (class "Default")
      (node (ref "IC2") (pin "71") (pinfunction "(AD7)PA7_71") (pintype "bidirectional"))
    )
    (net (code "74") (name "unconnected-(IC2-(ADC0)PF0-Pad97)") (class "Default")
      (node (ref "IC2") (pin "97") (pinfunction "(ADC0)PF0_97") (pintype "bidirectional"))
    )
    (net (code "75") (name "unconnected-(IC2-(ADC1)PF1-Pad96)") (class "Default")
      (node (ref "IC2") (pin "96") (pinfunction "(ADC1)PF1_96") (pintype "bidirectional"))
    )
    (net (code "76") (name "unconnected-(IC2-(ADC2)PF2-Pad95)") (class "Default")
      (node (ref "IC2") (pin "95") (pinfunction "(ADC2)PF2_95") (pintype "bidirectional"))
    )
    (net (code "77") (name "unconnected-(IC2-(ADC3)PF3-Pad94)") (class "Default")
      (node (ref "IC2") (pin "94") (pinfunction "(ADC3)PF3_94") (pintype "bidirectional"))
    )
    (net (code "78") (name "unconnected-(IC2-(ADC4{slash}TCK)PF4-Pad93)") (class "Default")
      (node (ref "IC2") (pin "93") (pinfunction "(ADC4/TCK)PF4_93") (pintype "bidirectional"))
    )
    (net (code "79") (name "unconnected-(IC2-(ADC5{slash}TMS)PF5-Pad92)") (class "Default")
      (node (ref "IC2") (pin "92") (pinfunction "(ADC5/TMS)PF5_92") (pintype "bidirectional"))
    )
    (net (code "80") (name "unconnected-(IC2-(ADC6{slash}TDO)PF6-Pad91)") (class "Default")
      (node (ref "IC2") (pin "91") (pinfunction "(ADC6/TDO)PF6_91") (pintype "bidirectional"))
    )
    (net (code "81") (name "unconnected-(IC2-(ADC7{slash}TDI)PF7-Pad90)") (class "Default")
      (node (ref "IC2") (pin "90") (pinfunction "(ADC7/TDI)PF7_90") (pintype "bidirectional"))
    )
    (net (code "82") (name "unconnected-(IC2-(ALE)PG2-Pad70)") (class "Default")
      (node (ref "IC2") (pin "70") (pinfunction "(ALE)PG2_70") (pintype "bidirectional"))
    )
    (net (code "83") (name "unconnected-(IC2-(CLKO{slash}ICP3{slash}INT7)PE7-Pad9)") (class "Default")
      (node (ref "IC2") (pin "9") (pinfunction "(CLKO/ICP3/INT7)PE7_9") (pintype "bidirectional"))
    )
    (net (code "84") (name "unconnected-(IC2-(ICP1)PD4-Pad47)") (class "Default")
      (node (ref "IC2") (pin "47") (pinfunction "(ICP1)PD4_47") (pintype "bidirectional"))
    )
    (net (code "85") (name "unconnected-(IC2-(OC0A{slash}OC1C{slash}PCINT7)PB7-Pad26)") (class "Default")
      (node (ref "IC2") (pin "26") (pinfunction "(OC0A/OC1C/PCINT7)PB7_26") (pintype "bidirectional"))
    )
    (net (code "86") (name "unconnected-(IC2-(OC0B)PG5-Pad1)") (class "Default")
      (node (ref "IC2") (pin "1") (pinfunction "(OC0B)PG5_1") (pintype "bidirectional"))
    )
    (net (code "87") (name "unconnected-(IC2-(OC1A{slash}PCINT5)PB5-Pad24)") (class "Default")
      (node (ref "IC2") (pin "24") (pinfunction "(OC1A/PCINT5)PB5_24") (pintype "bidirectional"))
    )
    (net (code "88") (name "unconnected-(IC2-(OC1B{slash}PCINT6)PB6-Pad25)") (class "Default")
      (node (ref "IC2") (pin "25") (pinfunction "(OC1B/PCINT6)PB6_25") (pintype "bidirectional"))
    )
    (net (code "89") (name "unconnected-(IC2-(OC2A{slash}PCINT4)PB4-Pad23)") (class "Default")
      (node (ref "IC2") (pin "23") (pinfunction "(OC2A/PCINT4)PB4_23") (pintype "bidirectional"))
    )
    (net (code "90") (name "unconnected-(IC2-(OC3C{slash}INT5)PE5-Pad7)") (class "Default")
      (node (ref "IC2") (pin "7") (pinfunction "(OC3C/INT5)PE5_7") (pintype "bidirectional"))
    )
    (net (code "91") (name "unconnected-(IC2-(RD)PG1-Pad52)") (class "Default")
      (node (ref "IC2") (pin "52") (pinfunction "(RD)PG1_52") (pintype "bidirectional"))
    )
    (net (code "92") (name "unconnected-(IC2-(RXD0{slash}PCIN8)PE0-Pad2)") (class "Default")
      (node (ref "IC2") (pin "2") (pinfunction "(RXD0/PCIN8)PE0_2") (pintype "bidirectional"))
    )
    (net (code "93") (name "unconnected-(IC2-(RXD1{slash}INT2)PD2-Pad45)") (class "Default")
      (node (ref "IC2") (pin "45") (pinfunction "(RXD1/INT2)PD2_45") (pintype "bidirectional"))
    )
    (net (code "94") (name "unconnected-(IC2-(SCL{slash}INT0)PD0-Pad43)") (class "Default")
      (node (ref "IC2") (pin "43") (pinfunction "(SCL/INT0)PD0_43") (pintype "bidirectional"))
    )
    (net (code "95") (name "unconnected-(IC2-(SDA{slash}INT1)PD1-Pad44)") (class "Default")
      (node (ref "IC2") (pin "44") (pinfunction "(SDA/INT1)PD1_44") (pintype "bidirectional"))
    )
    (net (code "96") (name "unconnected-(IC2-(T0)PD7-Pad50)") (class "Default")
      (node (ref "IC2") (pin "50") (pinfunction "(T0)PD7_50") (pintype "bidirectional"))
    )
    (net (code "97") (name "unconnected-(IC2-(T1)PD6-Pad49)") (class "Default")
      (node (ref "IC2") (pin "49") (pinfunction "(T1)PD6_49") (pintype "bidirectional"))
    )
    (net (code "98") (name "unconnected-(IC2-(T3{slash}INT6)PE6-Pad8)") (class "Default")
      (node (ref "IC2") (pin "8") (pinfunction "(T3/INT6)PE6_8") (pintype "bidirectional"))
    )
    (net (code "99") (name "unconnected-(IC2-(TOSC1)PG4-Pad29)") (class "Default")
      (node (ref "IC2") (pin "29") (pinfunction "(TOSC1)PG4_29") (pintype "bidirectional"))
    )
    (net (code "100") (name "unconnected-(IC2-(TOSC2)PG3-Pad28)") (class "Default")
      (node (ref "IC2") (pin "28") (pinfunction "(TOSC2)PG3_28") (pintype "bidirectional"))
    )
    (net (code "101") (name "unconnected-(IC2-(TXD0)PE1-Pad3)") (class "Default")
      (node (ref "IC2") (pin "3") (pinfunction "(TXD0)PE1_3") (pintype "bidirectional"))
    )
    (net (code "102") (name "unconnected-(IC2-(TXD1{slash}INT3)PD3-Pad46)") (class "Default")
      (node (ref "IC2") (pin "46") (pinfunction "(TXD1/INT3)PD3_46") (pintype "bidirectional"))
    )
    (net (code "103") (name "unconnected-(IC2-(WR)PG0-Pad51)") (class "Default")
      (node (ref "IC2") (pin "51") (pinfunction "(WR)PG0_51") (pintype "bidirectional"))
    )
    (net (code "104") (name "unconnected-(IC2-(XCK1)PD5-Pad48)") (class "Default")
      (node (ref "IC2") (pin "48") (pinfunction "(XCK1)PD5_48") (pintype "bidirectional"))
    )
    (net (code "105") (name "unconnected-(IC2-AREF-Pad98)") (class "Default")
      (node (ref "IC2") (pin "98") (pinfunction "AREF_98") (pintype "bidirectional"))
    )
    (net (code "106") (name "unconnected-(IC2-PH0(RXD2)-Pad12)") (class "Default")
      (node (ref "IC2") (pin "12") (pinfunction "PH0(RXD2)_12") (pintype "bidirectional"))
    )
    (net (code "107") (name "unconnected-(IC2-PH4(OC4B)-Pad16)") (class "Default")
      (node (ref "IC2") (pin "16") (pinfunction "PH4(OC4B)_16") (pintype "bidirectional"))
    )
    (net (code "108") (name "unconnected-(IC2-PH5(OC4C)-Pad17)") (class "Default")
      (node (ref "IC2") (pin "17") (pinfunction "PH5(OC4C)_17") (pintype "bidirectional"))
    )
    (net (code "109") (name "unconnected-(IC2-PH6(OC2B)-Pad18)") (class "Default")
      (node (ref "IC2") (pin "18") (pinfunction "PH6(OC2B)_18") (pintype "bidirectional"))
    )
    (net (code "110") (name "unconnected-(IC2-PH7(T4)-Pad27)") (class "Default")
      (node (ref "IC2") (pin "27") (pinfunction "PH7(T4)_27") (pintype "bidirectional"))
    )
    (net (code "111") (name "unconnected-(IC2-PJ2(XCK3{slash}PCINT11)-Pad65)") (class "Default")
      (node (ref "IC2") (pin "65") (pinfunction "PJ2(XCK3/PCINT11)_65") (pintype "bidirectional"))
    )
    (net (code "112") (name "unconnected-(IC2-PJ3(PCINT12)-Pad66)") (class "Default")
      (node (ref "IC2") (pin "66") (pinfunction "PJ3(PCINT12)_66") (pintype "bidirectional"))
    )
    (net (code "113") (name "unconnected-(IC2-PJ4(PCINT13)-Pad67)") (class "Default")
      (node (ref "IC2") (pin "67") (pinfunction "PJ4(PCINT13)_67") (pintype "bidirectional"))
    )
    (net (code "114") (name "unconnected-(IC2-PJ5(PCINT14)-Pad68)") (class "Default")
      (node (ref "IC2") (pin "68") (pinfunction "PJ5(PCINT14)_68") (pintype "bidirectional"))
    )
    (net (code "115") (name "unconnected-(IC2-PJ6(PCINT15)-Pad69)") (class "Default")
      (node (ref "IC2") (pin "69") (pinfunction "PJ6(PCINT15)_69") (pintype "bidirectional"))
    )
    (net (code "116") (name "unconnected-(IC2-PJ7-Pad79)") (class "Default")
      (node (ref "IC2") (pin "79") (pinfunction "PJ7_79") (pintype "bidirectional"))
    )
    (net (code "117") (name "unconnected-(IC2-PK0(ADC8{slash}PCINT16)-Pad89)") (class "Default")
      (node (ref "IC2") (pin "89") (pinfunction "PK0(ADC8/PCINT16)_89") (pintype "bidirectional"))
    )
    (net (code "118") (name "unconnected-(IC2-PK1(ADC9{slash}PCINT17)-Pad88)") (class "Default")
      (node (ref "IC2") (pin "88") (pinfunction "PK1(ADC9/PCINT17)_88") (pintype "bidirectional"))
    )
    (net (code "119") (name "unconnected-(IC2-PK2(ADC10{slash}PCINT18)-Pad87)") (class "Default")
      (node (ref "IC2") (pin "87") (pinfunction "PK2(ADC10/PCINT18)_87") (pintype "bidirectional"))
    )
    (net (code "120") (name "unconnected-(IC2-PK3(ADC11{slash}PCINT19)-Pad86)") (class "Default")
      (node (ref "IC2") (pin "86") (pinfunction "PK3(ADC11/PCINT19)_86") (pintype "bidirectional"))
    )
    (net (code "121") (name "unconnected-(IC2-PK4(ADC12{slash}PCINT20)-Pad85)") (class "Default")
      (node (ref "IC2") (pin "85") (pinfunction "PK4(ADC12/PCINT20)_85") (pintype "bidirectional"))
    )
    (net (code "122") (name "unconnected-(IC2-PK5(ADC13{slash}PCINT21)-Pad84)") (class "Default")
      (node (ref "IC2") (pin "84") (pinfunction "PK5(ADC13/PCINT21)_84") (pintype "bidirectional"))
    )
    (net (code "123") (name "unconnected-(IC2-PK6(ADC14{slash}PCINT22)-Pad83)") (class "Default")
      (node (ref "IC2") (pin "83") (pinfunction "PK6(ADC14/PCINT22)_83") (pintype "bidirectional"))
    )
    (net (code "124") (name "unconnected-(IC2-PK7(ADC15{slash}PCINT23)-Pad82)") (class "Default")
      (node (ref "IC2") (pin "82") (pinfunction "PK7(ADC15/PCINT23)_82") (pintype "bidirectional"))
    )
    (net (code "125") (name "unconnected-(IC2-PL0(ICP4)-Pad35)") (class "Default")
      (node (ref "IC2") (pin "35") (pinfunction "PL0(ICP4)_35") (pintype "bidirectional"))
    )
    (net (code "126") (name "unconnected-(IC2-PL1(ICP5)-Pad36)") (class "Default")
      (node (ref "IC2") (pin "36") (pinfunction "PL1(ICP5)_36") (pintype "bidirectional"))
    )
    (net (code "127") (name "unconnected-(IC2-PL2(T5)-Pad37)") (class "Default")
      (node (ref "IC2") (pin "37") (pinfunction "PL2(T5)_37") (pintype "bidirectional"))
    )
    (net (code "128") (name "unconnected-(IC2-PL3(OC5A)-Pad38)") (class "Default")
      (node (ref "IC2") (pin "38") (pinfunction "PL3(OC5A)_38") (pintype "bidirectional"))
    )
    (net (code "129") (name "unconnected-(IC2-PL4(OC5B)-Pad39)") (class "Default")
      (node (ref "IC2") (pin "39") (pinfunction "PL4(OC5B)_39") (pintype "bidirectional"))
    )
    (net (code "130") (name "unconnected-(IC2-PL5(OC5C)-Pad40)") (class "Default")
      (node (ref "IC2") (pin "40") (pinfunction "PL5(OC5C)_40") (pintype "bidirectional"))
    )
    (net (code "131") (name "unconnected-(IC2-PL6-Pad41)") (class "Default")
      (node (ref "IC2") (pin "41") (pinfunction "PL6_41") (pintype "bidirectional"))
    )
    (net (code "132") (name "unconnected-(IC2-PL7-Pad42)") (class "Default")
      (node (ref "IC2") (pin "42") (pinfunction "PL7_42") (pintype "bidirectional"))
    )
    (net (code "133") (name "unconnected-(IC7-CTS-Pad11)") (class "Default")
      (node (ref "IC7") (pin "11") (pinfunction "CTS_11") (pintype "input"))
    )
    (net (code "134") (name "unconnected-(IC7-DCD-Pad10)") (class "Default")
      (node (ref "IC7") (pin "10") (pinfunction "DCD_10") (pintype "input"))
    )
    (net (code "135") (name "unconnected-(IC7-DSR-Pad9)") (class "Default")
      (node (ref "IC7") (pin "9") (pinfunction "DSR_9") (pintype "input"))
    )
    (net (code "136") (name "unconnected-(IC7-OSCI-Pad27)") (class "Default")
      (node (ref "IC7") (pin "27") (pinfunction "OSCI_27") (pintype "input"))
    )
    (net (code "137") (name "unconnected-(IC7-OSCO-Pad28)") (class "Default")
      (node (ref "IC7") (pin "28") (pinfunction "OSCO_28") (pintype "output"))
    )
    (net (code "138") (name "unconnected-(IC7-PWREN-Pad14)") (class "Default")
      (node (ref "IC7") (pin "14") (pinfunction "PWREN_14") (pintype "input"))
    )
    (net (code "139") (name "unconnected-(IC7-RI-Pad6)") (class "Default")
      (node (ref "IC7") (pin "6") (pinfunction "RI_6") (pintype "input"))
    )
    (net (code "140") (name "unconnected-(IC7-RTS-Pad3)") (class "Default")
      (node (ref "IC7") (pin "3") (pinfunction "RTS_3") (pintype "output"))
    )
    (net (code "141") (name "unconnected-(IC7-SLEEP-Pad12)") (class "Default")
      (node (ref "IC7") (pin "12") (pinfunction "SLEEP_12") (pintype "input"))
    )
    (net (code "142") (name "unconnected-(IC7-TXDEN-Pad13)") (class "Default")
      (node (ref "IC7") (pin "13") (pinfunction "TXDEN_13") (pintype "input"))
    )
    (net (code "143") (name "unconnected-(K1-PadO)") (class "Default")
      (node (ref "K1") (pin "O") (pinfunction "O_O") (pintype "passive"))
    )
    (net (code "144") (name "unconnected-(K6-PadO)") (class "Default")
      (node (ref "K6") (pin "O") (pinfunction "O_O") (pintype "passive"))
    )
    (net (code "145") (name "unconnected-(LED1-DOUT-Pad2)") (class "Default")
      (node (ref "LED1") (pin "2") (pinfunction "DOUT_2") (pintype "output"))
    )
    (net (code "146") (name "unconnected-(U$2-D0{slash}RX1-PadD0)") (class "Default")
      (node (ref "U$2") (pin "D0") (pinfunction "D0/RX1_D0") (pintype "bidirectional"))
    )
    (net (code "147") (name "unconnected-(U$2-D1{slash}TX0-PadD1)") (class "Default")
      (node (ref "U$2") (pin "D1") (pinfunction "D1/TX0_D1") (pintype "bidirectional"))
    )
    (net (code "148") (name "unconnected-(U$2-D2{slash}FLAG-PadD2-FLAG)") (class "Default")
      (node (ref "U$2") (pin "D2-FLAG") (pinfunction "D2/FLAG_D2-FLAG") (pintype "bidirectional"))
    )
    (net (code "149") (name "unconnected-(U$2-D4{slash}BUSY-PadD4-BUSY)") (class "Default")
      (node (ref "U$2") (pin "D4-BUSY") (pinfunction "D4/BUSY_D4-BUSY") (pintype "bidirectional"))
    )
    (net (code "150") (name "unconnected-(U$2-D9{slash}STCK-PadD9-STCK)") (class "Default")
      (node (ref "U$2") (pin "D9-STCK") (pinfunction "D9/STCK_D9-STCK") (pintype "bidirectional"))
    )
    (net (code "151") (name "unconnected-(U$2-PadA0)") (class "Default")
      (node (ref "U$2") (pin "A0") (pinfunction "A0_A0") (pintype "bidirectional"))
    )
    (net (code "152") (name "unconnected-(U$2-PadA1)") (class "Default")
      (node (ref "U$2") (pin "A1") (pinfunction "A1_A1") (pintype "bidirectional"))
    )
    (net (code "153") (name "unconnected-(U$2-PadA3)") (class "Default")
      (node (ref "U$2") (pin "A3") (pinfunction "A3_A3") (pintype "bidirectional"))
    )
    (net (code "154") (name "unconnected-(U$2-PadA4)") (class "Default")
      (node (ref "U$2") (pin "A4") (pinfunction "A4_A4") (pintype "bidirectional"))
    )
    (net (code "155") (name "unconnected-(U$2-PadA5)") (class "Default")
      (node (ref "U$2") (pin "A5") (pinfunction "A5_A5") (pintype "bidirectional"))
    )
    (net (code "156") (name "unconnected-(U$2-PadD3)") (class "Default")
      (node (ref "U$2") (pin "D3") (pinfunction "D3_D3") (pintype "bidirectional"))
    )
    (net (code "157") (name "unconnected-(U$2-PadD5)") (class "Default")
      (node (ref "U$2") (pin "D5") (pinfunction "D5_D5") (pintype "bidirectional"))
    )
    (net (code "158") (name "unconnected-(U$2-PadD6)") (class "Default")
      (node (ref "U$2") (pin "D6") (pinfunction "D6_D6") (pintype "bidirectional"))
    )
    (net (code "159") (name "unconnected-(U$2-PadD7)") (class "Default")
      (node (ref "U$2") (pin "D7") (pinfunction "D7_D7") (pintype "bidirectional"))
    )
    (net (code "160") (name "unconnected-(U$2-PadD10)") (class "Default")
      (node (ref "U$2") (pin "D10") (pinfunction "D10_D10") (pintype "bidirectional"))
    )
  )
)
